# BEE_BOARD_DECAWAVE.net
KiCad netlist of a schematic drawn in Altium Designer
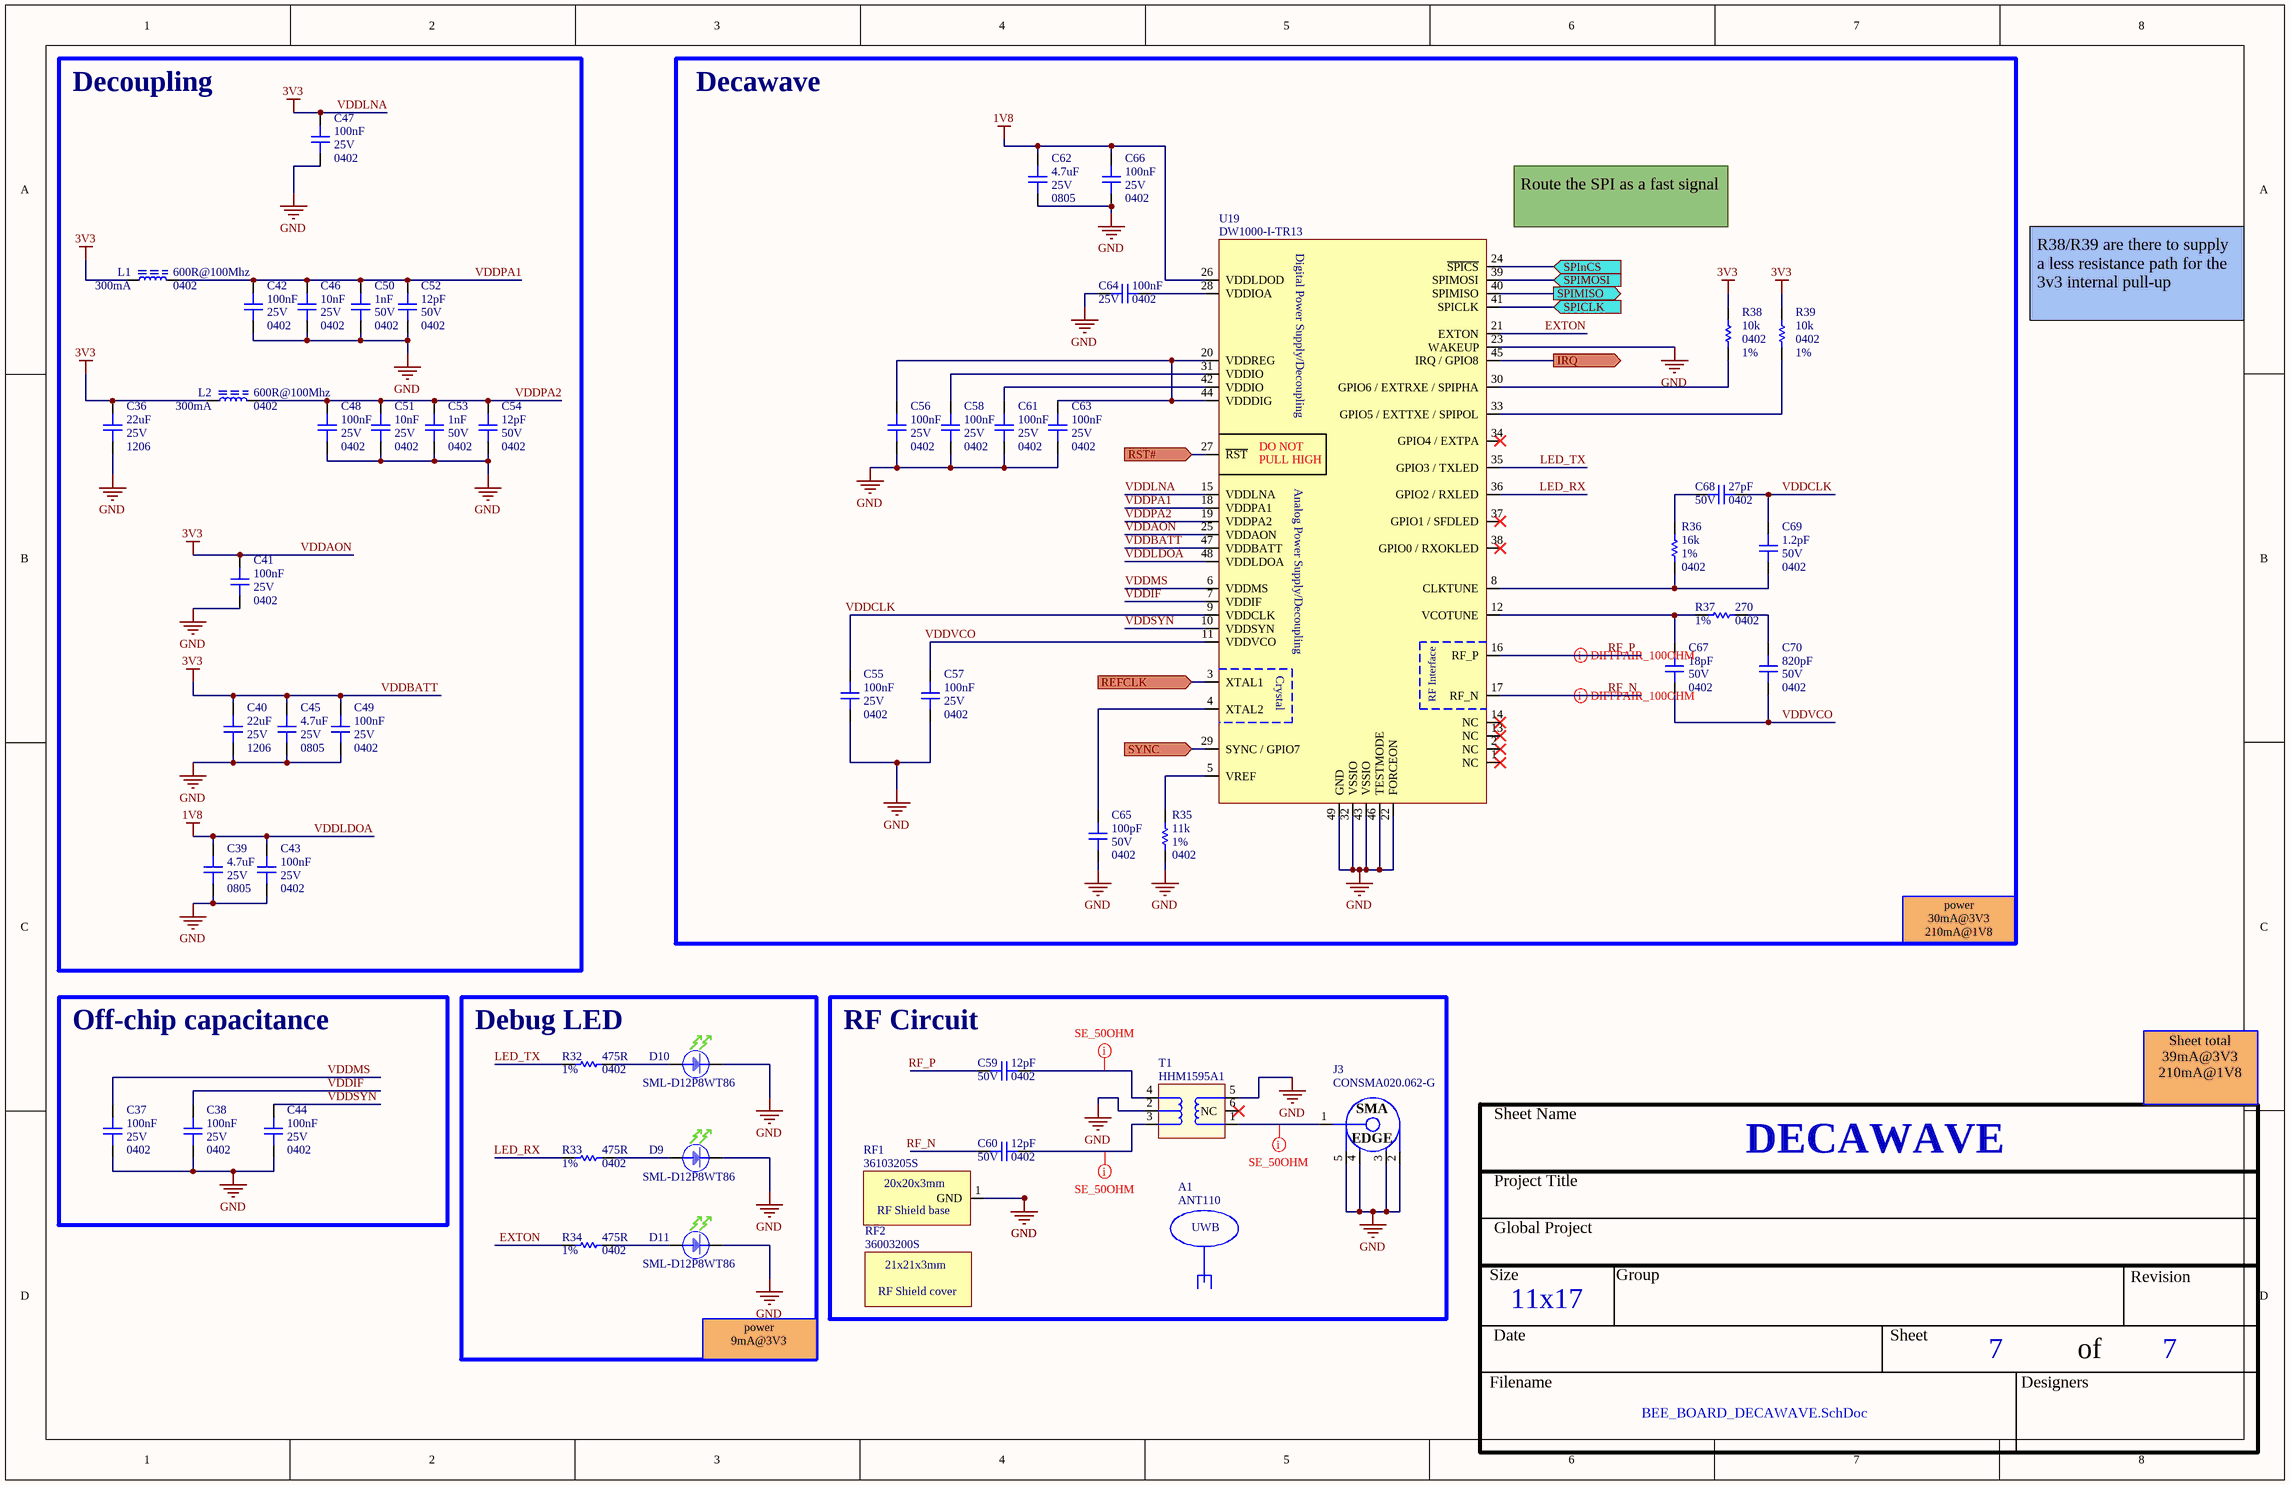
[diagram p0: BEE_BOARD_DECAWAVE.SchDoc]

(export (version "E")
  (design (tool "Eeschema 10.0.6"))
  (components
    (comp (ref "A1")
      (value "ANT110")
      (description "ANT - UWB antenna 3.2 to 7GHz")
      (fields
        (field (name "CREATEDBY/DATE") "Philippe Arsenault/2021-04-11")
        (field (name "VERIFIEDBY") "Louis-Daniel Gaulin / 14-04-2021")
      )
      (libsource (lib "SWARMUS_LIB") (part "ANT_ANT110"))
    )
    (comp (ref "C36")
      (value "22uF")
      (footprint "grams_master_lib_pcb:CAP_CER_1206")
      (description "CAP - CER 22uF 10% 25V X5R - 1206")
      (fields
        (field (name "TOLERANCE") "10%")
        (field (name "PACKAGE") "1206")
        (field (name "VOLTAGE RATING") "25V")
        (field (name "Comment") "CL31A226KAHNNNE")
        (field (name "CREATEDBY/DATE") "Philippe Arsenault/21 Janvier 2020")
        (field (name "VERIFIEDBY") "C.Paulin - 28/01/2020")
      )
      (libsource (lib "GRAMS_MASTER_LIB_SCH") (part "CAP_CER_CL31A226KAHNNNE"))
    )
    (comp (ref "C37")
      (value "100nF")
      (footprint "GRAMS_MASTER_LIB_PCB:CAP_CER_0402")
      (description "CAP - CER 0.1µF 10% 25V X7R - 0402")
      (fields
        (field (name "TOLERANCE") "10%")
        (field (name "PACKAGE") "0402")
        (field (name "VOLTAGE RATING") "25V")
        (field (name "Comment") "CGA2B3X7R1E104K050BB")
        (field (name "CREATEDBY/DATE") "Nicolas Roy 2018-11-07")
        (field (name "VERIFIEDBY") "Nicolas V. (2019-01-22)")
      )
      (libsource (lib "GRAMS_MASTER_LIB_SCH") (part "CAP_CER_CGA2B3X7R1E104K050BB"))
    )
    (comp (ref "C38")
      (value "100nF")
      (footprint "GRAMS_MASTER_LIB_PCB:CAP_CER_0402")
      (description "CAP - CER 0.1µF 10% 25V X7R - 0402")
      (fields
        (field (name "TOLERANCE") "10%")
        (field (name "PACKAGE") "0402")
        (field (name "VOLTAGE RATING") "25V")
        (field (name "Comment") "CGA2B3X7R1E104K050BB")
        (field (name "CREATEDBY/DATE") "Nicolas Roy 2018-11-07")
        (field (name "VERIFIEDBY") "Nicolas V. (2019-01-22)")
      )
      (libsource (lib "GRAMS_MASTER_LIB_SCH") (part "CAP_CER_CGA2B3X7R1E104K050BB"))
    )
    (comp (ref "C39")
      (value "4.7uF")
      (footprint "GRAMS_MASTER_LIB_PCB:CAP_CER_0805")
      (description "CAP - CER 4.7UF 10% 25V X7R - 0805")
      (fields
        (field (name "TOLERANCE") "10%")
        (field (name "PACKAGE") "0805")
        (field (name "VOLTAGE RATING") "25V")
        (field (name "Comment") "C2012X7R1E475K125AE")
        (field (name "CREATEDBY/DATE") "Keven Deslandes - 2018/11/09")
        (field (name "VERIFIEDBY") "Nicolas Roy - 2018/12/11")
      )
      (libsource (lib "GRAMS_MASTER_LIB_SCH") (part "CAP_CER_C2012X7R1E475K125AE"))
    )
    (comp (ref "C40")
      (value "22uF")
      (footprint "grams_master_lib_pcb:CAP_CER_1206")
      (description "CAP - CER 22uF 10% 25V X5R - 1206")
      (fields
        (field (name "TOLERANCE") "10%")
        (field (name "PACKAGE") "1206")
        (field (name "VOLTAGE RATING") "25V")
        (field (name "Comment") "CL31A226KAHNNNE")
        (field (name "CREATEDBY/DATE") "Philippe Arsenault/21 Janvier 2020")
        (field (name "VERIFIEDBY") "C.Paulin - 28/01/2020")
      )
      (libsource (lib "GRAMS_MASTER_LIB_SCH") (part "CAP_CER_CL31A226KAHNNNE"))
    )
    (comp (ref "C41")
      (value "100nF")
      (footprint "GRAMS_MASTER_LIB_PCB:CAP_CER_0402")
      (description "CAP - CER 0.1µF 10% 25V X7R - 0402")
      (fields
        (field (name "TOLERANCE") "10%")
        (field (name "PACKAGE") "0402")
        (field (name "VOLTAGE RATING") "25V")
        (field (name "Comment") "CGA2B3X7R1E104K050BB")
        (field (name "CREATEDBY/DATE") "Nicolas Roy 2018-11-07")
        (field (name "VERIFIEDBY") "Nicolas V. (2019-01-22)")
      )
      (libsource (lib "GRAMS_MASTER_LIB_SCH") (part "CAP_CER_CGA2B3X7R1E104K050BB"))
    )
    (comp (ref "C42")
      (value "100nF")
      (footprint "GRAMS_MASTER_LIB_PCB:CAP_CER_0402")
      (description "CAP - CER 0.1µF 10% 25V X7R - 0402")
      (fields
        (field (name "TOLERANCE") "10%")
        (field (name "PACKAGE") "0402")
        (field (name "VOLTAGE RATING") "25V")
        (field (name "Comment") "CGA2B3X7R1E104K050BB")
        (field (name "CREATEDBY/DATE") "Nicolas Roy 2018-11-07")
        (field (name "VERIFIEDBY") "Nicolas V. (2019-01-22)")
      )
      (libsource (lib "GRAMS_MASTER_LIB_SCH") (part "CAP_CER_CGA2B3X7R1E104K050BB"))
    )
    (comp (ref "C43")
      (value "100nF")
      (footprint "GRAMS_MASTER_LIB_PCB:CAP_CER_0402")
      (description "CAP - CER 0.1µF 10% 25V X7R - 0402")
      (fields
        (field (name "TOLERANCE") "10%")
        (field (name "PACKAGE") "0402")
        (field (name "VOLTAGE RATING") "25V")
        (field (name "Comment") "CGA2B3X7R1E104K050BB")
        (field (name "CREATEDBY/DATE") "Nicolas Roy 2018-11-07")
        (field (name "VERIFIEDBY") "Nicolas V. (2019-01-22)")
      )
      (libsource (lib "GRAMS_MASTER_LIB_SCH") (part "CAP_CER_CGA2B3X7R1E104K050BB"))
    )
    (comp (ref "C44")
      (value "100nF")
      (footprint "GRAMS_MASTER_LIB_PCB:CAP_CER_0402")
      (description "CAP - CER 0.1µF 10% 25V X7R - 0402")
      (fields
        (field (name "TOLERANCE") "10%")
        (field (name "PACKAGE") "0402")
        (field (name "VOLTAGE RATING") "25V")
        (field (name "Comment") "CGA2B3X7R1E104K050BB")
        (field (name "CREATEDBY/DATE") "Nicolas Roy 2018-11-07")
        (field (name "VERIFIEDBY") "Nicolas V. (2019-01-22)")
      )
      (libsource (lib "GRAMS_MASTER_LIB_SCH") (part "CAP_CER_CGA2B3X7R1E104K050BB"))
    )
    (comp (ref "C45")
      (value "4.7uF")
      (footprint "GRAMS_MASTER_LIB_PCB:CAP_CER_0805")
      (description "CAP - CER 4.7UF 10% 25V X7R - 0805")
      (fields
        (field (name "TOLERANCE") "10%")
        (field (name "PACKAGE") "0805")
        (field (name "VOLTAGE RATING") "25V")
        (field (name "Comment") "C2012X7R1E475K125AE")
        (field (name "CREATEDBY/DATE") "Keven Deslandes - 2018/11/09")
        (field (name "VERIFIEDBY") "Nicolas Roy - 2018/12/11")
      )
      (libsource (lib "GRAMS_MASTER_LIB_SCH") (part "CAP_CER_C2012X7R1E475K125AE"))
    )
    (comp (ref "C46")
      (value "10nF")
      (footprint "GRAMS_MASTER_LIB_PCB:CAP_CER_0402")
      (description "CAP - CER 10nF 10% 25V X7R - 0402")
      (fields
        (field (name "TOLERANCE") "10%")
        (field (name "PACKAGE") "0402")
        (field (name "VOLTAGE RATING") "25V")
        (field (name "Comment") "CL05B103KA5NNNC")
        (field (name "CREATEDBY/DATE") "Romain Espagnet 2018-07-16")
        (field (name "VERIFIEDBY") "Jonathan Bouchard 2018-07-30")
      )
      (libsource (lib "GRAMS_MASTER_LIB_SCH") (part "CAP_CER_CL05B103KA5NNNC"))
    )
    (comp (ref "C47")
      (value "100nF")
      (footprint "GRAMS_MASTER_LIB_PCB:CAP_CER_0402")
      (description "CAP - CER 0.1µF 10% 25V X7R - 0402")
      (fields
        (field (name "TOLERANCE") "10%")
        (field (name "PACKAGE") "0402")
        (field (name "VOLTAGE RATING") "25V")
        (field (name "Comment") "CGA2B3X7R1E104K050BB")
        (field (name "CREATEDBY/DATE") "Nicolas Roy 2018-11-07")
        (field (name "VERIFIEDBY") "Nicolas V. (2019-01-22)")
      )
      (libsource (lib "GRAMS_MASTER_LIB_SCH") (part "CAP_CER_CGA2B3X7R1E104K050BB"))
    )
    (comp (ref "C48")
      (value "100nF")
      (footprint "GRAMS_MASTER_LIB_PCB:CAP_CER_0402")
      (description "CAP - CER 0.1µF 10% 25V X7R - 0402")
      (fields
        (field (name "TOLERANCE") "10%")
        (field (name "PACKAGE") "0402")
        (field (name "VOLTAGE RATING") "25V")
        (field (name "Comment") "CGA2B3X7R1E104K050BB")
        (field (name "CREATEDBY/DATE") "Nicolas Roy 2018-11-07")
        (field (name "VERIFIEDBY") "Nicolas V. (2019-01-22)")
      )
      (libsource (lib "GRAMS_MASTER_LIB_SCH") (part "CAP_CER_CGA2B3X7R1E104K050BB"))
    )
    (comp (ref "C49")
      (value "100nF")
      (footprint "GRAMS_MASTER_LIB_PCB:CAP_CER_0402")
      (description "CAP - CER 0.1µF 10% 25V X7R - 0402")
      (fields
        (field (name "TOLERANCE") "10%")
        (field (name "PACKAGE") "0402")
        (field (name "VOLTAGE RATING") "25V")
        (field (name "Comment") "CGA2B3X7R1E104K050BB")
        (field (name "CREATEDBY/DATE") "Nicolas Roy 2018-11-07")
        (field (name "VERIFIEDBY") "Nicolas V. (2019-01-22)")
      )
      (libsource (lib "GRAMS_MASTER_LIB_SCH") (part "CAP_CER_CGA2B3X7R1E104K050BB"))
    )
    (comp (ref "C50")
      (value "1nF")
      (footprint "CAP_CER_0402")
      (description "CAP - CER 1nF 10% 50V X7R - 0402")
      (fields
        (field (name "TOLERANCE") "10%")
        (field (name "PACKAGE") "0402")
        (field (name "VOLTAGE RATING") "50V")
        (field (name "Comment") "CC0402KRX7R9BB102")
        (field (name "CREATEDBY/DATE") "Jonathan Bouchard 2019-04-06")
        (field (name "VERIFIEDBY") "Nicolas V. (2019-04-30)")
      )
      (libsource (lib "GRAMS_MASTER_LIB_SCH") (part "CAP_CER_CC0402KRX7R9BB102"))
    )
    (comp (ref "C51")
      (value "10nF")
      (footprint "GRAMS_MASTER_LIB_PCB:CAP_CER_0402")
      (description "CAP - CER 10nF 10% 25V X7R - 0402")
      (fields
        (field (name "TOLERANCE") "10%")
        (field (name "PACKAGE") "0402")
        (field (name "VOLTAGE RATING") "25V")
        (field (name "Comment") "CL05B103KA5NNNC")
        (field (name "CREATEDBY/DATE") "Romain Espagnet 2018-07-16")
        (field (name "VERIFIEDBY") "Jonathan Bouchard 2018-07-30")
      )
      (libsource (lib "GRAMS_MASTER_LIB_SCH") (part "CAP_CER_CL05B103KA5NNNC"))
    )
    (comp (ref "C52")
      (value "12pF")
      (footprint "SWARMUS_LIB:CAP_CER_0402")
      (description "CAP - CER 12pF 50V ±5% C0G, NP0 - 0402")
      (fields
        (field (name "TOLERANCE") "±5%")
        (field (name "PACKAGE") "0402")
        (field (name "VOLTAGE RATING") "50V")
        (field (name "Comment") "CC0402JRNPO9BN120")
        (field (name "CREATEDBY/DATE") "Philippe Arsenault/ 2020-07-24")
        (field (name "VERIFIEDBY") "Louis-Daniel Gaulin / 2020-07-29")
      )
      (libsource (lib "SWARMUS_LIB") (part "CAP_CER_CC0402JRNPO9BN120"))
    )
    (comp (ref "C53")
      (value "1nF")
      (footprint "CAP_CER_0402")
      (description "CAP - CER 1nF 10% 50V X7R - 0402")
      (fields
        (field (name "TOLERANCE") "10%")
        (field (name "PACKAGE") "0402")
        (field (name "VOLTAGE RATING") "50V")
        (field (name "Comment") "CC0402KRX7R9BB102")
        (field (name "CREATEDBY/DATE") "Jonathan Bouchard 2019-04-06")
        (field (name "VERIFIEDBY") "Nicolas V. (2019-04-30)")
      )
      (libsource (lib "GRAMS_MASTER_LIB_SCH") (part "CAP_CER_CC0402KRX7R9BB102"))
    )
    (comp (ref "C54")
      (value "12pF")
      (footprint "SWARMUS_LIB:CAP_CER_0402")
      (description "CAP - CER 12pF 50V ±5% C0G, NP0 - 0402")
      (fields
        (field (name "TOLERANCE") "±5%")
        (field (name "PACKAGE") "0402")
        (field (name "VOLTAGE RATING") "50V")
        (field (name "Comment") "CC0402JRNPO9BN120")
        (field (name "CREATEDBY/DATE") "Philippe Arsenault/ 2020-07-24")
        (field (name "VERIFIEDBY") "Louis-Daniel Gaulin / 2020-07-29")
      )
      (libsource (lib "SWARMUS_LIB") (part "CAP_CER_CC0402JRNPO9BN120"))
    )
    (comp (ref "C55")
      (value "100nF")
      (footprint "GRAMS_MASTER_LIB_PCB:CAP_CER_0402")
      (description "CAP - CER 0.1µF 10% 25V X7R - 0402")
      (fields
        (field (name "TOLERANCE") "10%")
        (field (name "PACKAGE") "0402")
        (field (name "VOLTAGE RATING") "25V")
        (field (name "Comment") "CGA2B3X7R1E104K050BB")
        (field (name "CREATEDBY/DATE") "Nicolas Roy 2018-11-07")
        (field (name "VERIFIEDBY") "Nicolas V. (2019-01-22)")
      )
      (libsource (lib "GRAMS_MASTER_LIB_SCH") (part "CAP_CER_CGA2B3X7R1E104K050BB"))
    )
    (comp (ref "C56")
      (value "100nF")
      (footprint "GRAMS_MASTER_LIB_PCB:CAP_CER_0402")
      (description "CAP - CER 0.1µF 10% 25V X7R - 0402")
      (fields
        (field (name "TOLERANCE") "10%")
        (field (name "PACKAGE") "0402")
        (field (name "VOLTAGE RATING") "25V")
        (field (name "Comment") "CGA2B3X7R1E104K050BB")
        (field (name "CREATEDBY/DATE") "Nicolas Roy 2018-11-07")
        (field (name "VERIFIEDBY") "Nicolas V. (2019-01-22)")
      )
      (libsource (lib "GRAMS_MASTER_LIB_SCH") (part "CAP_CER_CGA2B3X7R1E104K050BB"))
    )
    (comp (ref "C57")
      (value "100nF")
      (footprint "GRAMS_MASTER_LIB_PCB:CAP_CER_0402")
      (description "CAP - CER 0.1µF 10% 25V X7R - 0402")
      (fields
        (field (name "TOLERANCE") "10%")
        (field (name "PACKAGE") "0402")
        (field (name "VOLTAGE RATING") "25V")
        (field (name "Comment") "CGA2B3X7R1E104K050BB")
        (field (name "CREATEDBY/DATE") "Nicolas Roy 2018-11-07")
        (field (name "VERIFIEDBY") "Nicolas V. (2019-01-22)")
      )
      (libsource (lib "GRAMS_MASTER_LIB_SCH") (part "CAP_CER_CGA2B3X7R1E104K050BB"))
    )
    (comp (ref "C58")
      (value "100nF")
      (footprint "GRAMS_MASTER_LIB_PCB:CAP_CER_0402")
      (description "CAP - CER 0.1µF 10% 25V X7R - 0402")
      (fields
        (field (name "TOLERANCE") "10%")
        (field (name "PACKAGE") "0402")
        (field (name "VOLTAGE RATING") "25V")
        (field (name "Comment") "CGA2B3X7R1E104K050BB")
        (field (name "CREATEDBY/DATE") "Nicolas Roy 2018-11-07")
        (field (name "VERIFIEDBY") "Nicolas V. (2019-01-22)")
      )
      (libsource (lib "GRAMS_MASTER_LIB_SCH") (part "CAP_CER_CGA2B3X7R1E104K050BB"))
    )
    (comp (ref "C59")
      (value "12pF")
      (footprint "SWARMUS_LIB:CAP_CER_0402")
      (description "CAP - CER 12pF 50V ±5% C0G, NP0 - 0402")
      (fields
        (field (name "TOLERANCE") "±5%")
        (field (name "PACKAGE") "0402")
        (field (name "VOLTAGE RATING") "50V")
        (field (name "Comment") "CC0402JRNPO9BN120")
        (field (name "CREATEDBY/DATE") "Philippe Arsenault/ 2020-07-24")
        (field (name "VERIFIEDBY") "Louis-Daniel Gaulin / 2020-07-29")
      )
      (libsource (lib "SWARMUS_LIB") (part "CAP_CER_CC0402JRNPO9BN120"))
    )
    (comp (ref "C60")
      (value "12pF")
      (footprint "SWARMUS_LIB:CAP_CER_0402")
      (description "CAP - CER 12pF 50V ±5% C0G, NP0 - 0402")
      (fields
        (field (name "TOLERANCE") "±5%")
        (field (name "PACKAGE") "0402")
        (field (name "VOLTAGE RATING") "50V")
        (field (name "Comment") "CC0402JRNPO9BN120")
        (field (name "CREATEDBY/DATE") "Philippe Arsenault/ 2020-07-24")
        (field (name "VERIFIEDBY") "Louis-Daniel Gaulin / 2020-07-29")
      )
      (libsource (lib "SWARMUS_LIB") (part "CAP_CER_CC0402JRNPO9BN120"))
    )
    (comp (ref "C61")
      (value "100nF")
      (footprint "GRAMS_MASTER_LIB_PCB:CAP_CER_0402")
      (description "CAP - CER 0.1µF 10% 25V X7R - 0402")
      (fields
        (field (name "TOLERANCE") "10%")
        (field (name "PACKAGE") "0402")
        (field (name "VOLTAGE RATING") "25V")
        (field (name "Comment") "CGA2B3X7R1E104K050BB")
        (field (name "CREATEDBY/DATE") "Nicolas Roy 2018-11-07")
        (field (name "VERIFIEDBY") "Nicolas V. (2019-01-22)")
      )
      (libsource (lib "GRAMS_MASTER_LIB_SCH") (part "CAP_CER_CGA2B3X7R1E104K050BB"))
    )
    (comp (ref "C62")
      (value "4.7uF")
      (footprint "GRAMS_MASTER_LIB_PCB:CAP_CER_0805")
      (description "CAP - CER 4.7UF 10% 25V X7R - 0805")
      (fields
        (field (name "TOLERANCE") "10%")
        (field (name "PACKAGE") "0805")
        (field (name "VOLTAGE RATING") "25V")
        (field (name "Comment") "C2012X7R1E475K125AE")
        (field (name "CREATEDBY/DATE") "Keven Deslandes - 2018/11/09")
        (field (name "VERIFIEDBY") "Nicolas Roy - 2018/12/11")
      )
      (libsource (lib "GRAMS_MASTER_LIB_SCH") (part "CAP_CER_C2012X7R1E475K125AE"))
    )
    (comp (ref "C63")
      (value "100nF")
      (footprint "GRAMS_MASTER_LIB_PCB:CAP_CER_0402")
      (description "CAP - CER 0.1µF 10% 25V X7R - 0402")
      (fields
        (field (name "TOLERANCE") "10%")
        (field (name "PACKAGE") "0402")
        (field (name "VOLTAGE RATING") "25V")
        (field (name "Comment") "CGA2B3X7R1E104K050BB")
        (field (name "CREATEDBY/DATE") "Nicolas Roy 2018-11-07")
        (field (name "VERIFIEDBY") "Nicolas V. (2019-01-22)")
      )
      (libsource (lib "GRAMS_MASTER_LIB_SCH") (part "CAP_CER_CGA2B3X7R1E104K050BB"))
    )
    (comp (ref "C64")
      (value "100nF")
      (footprint "GRAMS_MASTER_LIB_PCB:CAP_CER_0402")
      (description "CAP - CER 0.1µF 10% 25V X7R - 0402")
      (fields
        (field (name "TOLERANCE") "10%")
        (field (name "PACKAGE") "0402")
        (field (name "VOLTAGE RATING") "25V")
        (field (name "Comment") "CGA2B3X7R1E104K050BB")
        (field (name "CREATEDBY/DATE") "Nicolas Roy 2018-11-07")
        (field (name "VERIFIEDBY") "Nicolas V. (2019-01-22)")
      )
      (libsource (lib "GRAMS_MASTER_LIB_SCH") (part "CAP_CER_CGA2B3X7R1E104K050BB"))
    )
    (comp (ref "C65")
      (value "100pF")
      (footprint "SWARMUS_LIB:CAP_CER_0402")
      (description "CAP - CER 100pF 50V ±5% C0G,CP0 - 0402")
      (fields
        (field (name "TOLERANCE") "±5%")
        (field (name "PACKAGE") "0402")
        (field (name "VOLTAGE RATING") "50V")
        (field (name "Comment") "CC0402JRNPO9BN101")
        (field (name "CREATEDBY/DATE") "Philippe Arsenault/ 2020-07-24")
        (field (name "VERIFIEDBY") "Louis-Daniel Gaulin / 2020-07-29")
      )
      (libsource (lib "SWARMUS_LIB") (part "CAP_CER_CC0402JRNPO9BN101"))
    )
    (comp (ref "C66")
      (value "100nF")
      (footprint "GRAMS_MASTER_LIB_PCB:CAP_CER_0402")
      (description "CAP - CER 0.1µF 10% 25V X7R - 0402")
      (fields
        (field (name "TOLERANCE") "10%")
        (field (name "PACKAGE") "0402")
        (field (name "VOLTAGE RATING") "25V")
        (field (name "Comment") "CGA2B3X7R1E104K050BB")
        (field (name "CREATEDBY/DATE") "Nicolas Roy 2018-11-07")
        (field (name "VERIFIEDBY") "Nicolas V. (2019-01-22)")
      )
      (libsource (lib "GRAMS_MASTER_LIB_SCH") (part "CAP_CER_CGA2B3X7R1E104K050BB"))
    )
    (comp (ref "C67")
      (value "18pF")
      (footprint "CAP_CER_0402")
      (description "CAP - CER 18pF 50V C0G, NPO - 0402")
      (fields
        (field (name "TOLERANCE") "2%")
        (field (name "PACKAGE") "0402")
        (field (name "VOLTAGE RATING") "50V")
        (field (name "Comment") "GRM1555C1H180GA01D")
        (field (name "CREATEDBY/DATE") "Tommy Rossignol / 2018-11-20")
        (field (name "VERIFIEDBY") "Caroline Paulin - 13 fév 2019")
      )
      (libsource (lib "GRAMS_MASTER_LIB_SCH") (part "CAP_CER_GRM1555C1H180GA01D"))
    )
    (comp (ref "C68")
      (value "27pF")
      (footprint "SWARMUS_LIB:CAP_CER_0402")
      (description "CAP - CER 27pF 50V ±5% C0G, NP0 - 0402")
      (fields
        (field (name "TOLERANCE") "±5%")
        (field (name "PACKAGE") "0402")
        (field (name "VOLTAGE RATING") "50V")
        (field (name "Comment") "CC0402JRNPO9BN270")
        (field (name "CREATEDBY/DATE") "Philippe Arsenault/ 2020-07-24")
        (field (name "VERIFIEDBY") "Louis-Daniel Gaulin / 2020-07-29")
      )
      (libsource (lib "SWARMUS_LIB") (part "CAP_CER_CC0402JRNPO9BN270"))
    )
    (comp (ref "C69")
      (value "1.2pF")
      (footprint "SWARMUS_LIB:CAP_CER_0402")
      (description "CAP - CER 1.2pF 50V ±0.25pF C0G, NP0 - 0402")
      (fields
        (field (name "TOLERANCE") "±0.25pF")
        (field (name "PACKAGE") "0402")
        (field (name "VOLTAGE RATING") "50V")
        (field (name "Comment") "C0402C129C5GACTU")
        (field (name "CREATEDBY/DATE") "Philippe Arsenault/ 2020-07-24")
        (field (name "VERIFIEDBY") "Louis-Daniel Gaulin / 2020-07-29")
      )
      (libsource (lib "SWARMUS_LIB") (part "CAP_CER_C0402C129C5GACTU"))
    )
    (comp (ref "C70")
      (value "820pF")
      (footprint "SWARMUS_LIB:CAP_CER_0402")
      (description "CAP - CER 820pF 50V ±10% X7R - 0402")
      (fields
        (field (name "TOLERANCE") "±10%")
        (field (name "PACKAGE") "0402")
        (field (name "VOLTAGE RATING") "50V")
        (field (name "Comment") "CC0402KRX7R9BB821")
        (field (name "CREATEDBY/DATE") "Philippe Arsenault/ 2020-07-24")
        (field (name "VERIFIEDBY") "Louis-Daniel Gaulin / 2020-07-29")
      )
      (libsource (lib "SWARMUS_LIB") (part "CAP_CER_CC0402KRX7R9BB821"))
    )
    (comp (ref "D9")
      (value "SML-D12P8WT86")
      (footprint "GRAMS_MASTER_LIB_PCB:LED_SML-D12P8WT86")
      (description "LED - GREEN DIFFUSED 0603 SMD - 0603")
      (fields
        (field (name "CREATEDBY/DATE") "Keven Deslandes - 2018/11/21")
        (field (name "VERIFIEDBY") "Caroline Paulin - 13 février 2019")
      )
      (libsource (lib "GRAMS_MASTER_LIB_SCH") (part "LED_SML-D12P8WT86"))
    )
    (comp (ref "D10")
      (value "SML-D12P8WT86")
      (footprint "GRAMS_MASTER_LIB_PCB:LED_SML-D12P8WT86")
      (description "LED - GREEN DIFFUSED 0603 SMD - 0603")
      (fields
        (field (name "CREATEDBY/DATE") "Keven Deslandes - 2018/11/21")
        (field (name "VERIFIEDBY") "Caroline Paulin - 13 février 2019")
      )
      (libsource (lib "GRAMS_MASTER_LIB_SCH") (part "LED_SML-D12P8WT86"))
    )
    (comp (ref "D11")
      (value "SML-D12P8WT86")
      (footprint "GRAMS_MASTER_LIB_PCB:LED_SML-D12P8WT86")
      (description "LED - GREEN DIFFUSED 0603 SMD - 0603")
      (fields
        (field (name "CREATEDBY/DATE") "Keven Deslandes - 2018/11/21")
        (field (name "VERIFIEDBY") "Caroline Paulin - 13 février 2019")
      )
      (libsource (lib "GRAMS_MASTER_LIB_SCH") (part "LED_SML-D12P8WT86"))
    )
    (comp (ref "J3")
      (value "CONSMA020.062-G")
      (footprint "CON_SMA_CONSMA020.062-G")
      (description "CON_SMA FML EDGE MNT 0.062\" PCB - 5-SMD")
      (fields (field (name "CREATEDBY/DATE") "Philippe Arsenault/2021-03-26"))
      (libsource (lib "SWARMUS_LIB") (part "CON_SMA_CONSMA020.062-G"))
    )
    (comp (ref "L1")
      (value "600R@100Mhz")
      (footprint "FER_0402")
      (description "FER - FERRITE BEAD 600 OHM@100MHz - 0402")
      (fields
        (field (name "CURRENT RATING") "300mA")
        (field (name "PACKAGE") "0402")
        (field (name "Comment") "BLM15AG601SN1D")
        (field (name "CREATEDBY/DATE") "Philippe Arsenault/2020-07-24")
      )
      (libsource (lib "a_Valider_PA") (part "FER_BLM15AG601SN1D"))
    )
    (comp (ref "L2")
      (value "600R@100Mhz")
      (footprint "FER_0402")
      (description "FER - FERRITE BEAD 600 OHM@100MHz - 0402")
      (fields
        (field (name "CURRENT RATING") "300mA")
        (field (name "PACKAGE") "0402")
        (field (name "Comment") "BLM15AG601SN1D")
        (field (name "CREATEDBY/DATE") "Philippe Arsenault/2020-07-24")
      )
      (libsource (lib "a_Valider_PA") (part "FER_BLM15AG601SN1D"))
    )
    (comp (ref "R32")
      (value "475R")
      (footprint "GRAMS_MASTER_LIB_PCB:RES_0402")
      (description "RES - 475R 1% 1/10W- 0402")
      (fields
        (field (name "TOLERANCE") "1%")
        (field (name "PACKAGE") "0402")
        (field (name "Comment") "ERJ-2RKF4750X")
        (field (name "CREATEDBY/DATE") "Keven Deslandes 2018-10-17")
        (field (name "VERIFIEDBY") "Carolilne Paulin - 18/12/2018")
      )
      (libsource (lib "GRAMS_MASTER_LIB_SCH") (part "RES_ERJ-2RKF4750X"))
    )
    (comp (ref "R33")
      (value "475R")
      (footprint "GRAMS_MASTER_LIB_PCB:RES_0402")
      (description "RES - 475R 1% 1/10W- 0402")
      (fields
        (field (name "TOLERANCE") "1%")
        (field (name "PACKAGE") "0402")
        (field (name "Comment") "ERJ-2RKF4750X")
        (field (name "CREATEDBY/DATE") "Keven Deslandes 2018-10-17")
        (field (name "VERIFIEDBY") "Carolilne Paulin - 18/12/2018")
      )
      (libsource (lib "GRAMS_MASTER_LIB_SCH") (part "RES_ERJ-2RKF4750X"))
    )
    (comp (ref "R34")
      (value "475R")
      (footprint "GRAMS_MASTER_LIB_PCB:RES_0402")
      (description "RES - 475R 1% 1/10W- 0402")
      (fields
        (field (name "TOLERANCE") "1%")
        (field (name "PACKAGE") "0402")
        (field (name "Comment") "ERJ-2RKF4750X")
        (field (name "CREATEDBY/DATE") "Keven Deslandes 2018-10-17")
        (field (name "VERIFIEDBY") "Carolilne Paulin - 18/12/2018")
      )
      (libsource (lib "GRAMS_MASTER_LIB_SCH") (part "RES_ERJ-2RKF4750X"))
    )
    (comp (ref "R35")
      (value "11k")
      (footprint "GRAMS_MASTER_LIB_PCB:RES_0402")
      (description "RES - 11K 1% 1/16W - 0402")
      (fields
        (field (name "TOLERANCE") "1%")
        (field (name "PACKAGE") "0402")
        (field (name "Comment") "RC0402FR-0711KL")
        (field (name "CREATEDBY/DATE") "Keven Deslandes 2018-10-15")
        (field (name "VERIFIEDBY") "Carolilne Paulin - 18/12/2018")
      )
      (libsource (lib "GRAMS_MASTER_LIB_SCH") (part "RES_RC0402FR-0711KL"))
    )
    (comp (ref "R36")
      (value "16k")
      (footprint "GRAMS_MASTER_LIB_PCB:RES_0402")
      (description "RES - 16k OHM 1% 1/16W - 0402")
      (fields
        (field (name "TOLERANCE") "1%")
        (field (name "PACKAGE") "0402")
        (field (name "Comment") "RC0402FR-0716KL")
        (field (name "CREATEDBY/DATE") "Nicolas Roy/18 oct. 2018")
        (field (name "VERIFIEDBY") "Caroline Paulin - 18/12/2018")
      )
      (libsource (lib "GRAMS_MASTER_LIB_SCH") (part "RES_RC0402FR-0716KL"))
    )
    (comp (ref "R37")
      (value "270")
      (footprint "FER_0402")
      (description "RES - 270R 1% 1/16W - 0402")
      (fields
        (field (name "TOLERANCE") "1%")
        (field (name "PACKAGE") "0402")
        (field (name "Comment") "RC0402FR-07270RL")
        (field (name "CREATEDBY/DATE") "Philippe Arsenault 2020-07-24")
        (field (name "VERIFIEDBY") "Louis-Daniel Gaulin / 03-10-2020")
      )
      (libsource (lib "SWARMUS_LIB") (part "RES_RC0402FR-07270RL"))
    )
    (comp (ref "R38")
      (value "10k")
      (footprint "GRAMS_MASTER_LIB_PCB:RES_0402")
      (description "RES - 10K OHMS 1% 1/16W - 0402")
      (fields
        (field (name "TOLERANCE") "1%")
        (field (name "PACKAGE") "0402")
        (field (name "Comment") "RC0402FR-0710KL")
        (field (name "CREATEDBY/DATE") "Nicolas V. (2018-11-20)")
        (field (name "VERIFIEDBY") "Nicolas V. (2018-11-20)")
      )
      (libsource (lib "GRAMS_MASTER_LIB_SCH") (part "RES_RC0402FR-0710KL"))
    )
    (comp (ref "R39")
      (value "10k")
      (footprint "GRAMS_MASTER_LIB_PCB:RES_0402")
      (description "RES - 10K OHMS 1% 1/16W - 0402")
      (fields
        (field (name "TOLERANCE") "1%")
        (field (name "PACKAGE") "0402")
        (field (name "Comment") "RC0402FR-0710KL")
        (field (name "CREATEDBY/DATE") "Nicolas V. (2018-11-20)")
        (field (name "VERIFIEDBY") "Nicolas V. (2018-11-20)")
      )
      (libsource (lib "GRAMS_MASTER_LIB_SCH") (part "RES_RC0402FR-0710KL"))
    )
    (comp (ref "RF1")
      (value "36103205S")
      (footprint "RF_SH_BASE_36103205S")
      (description "RF_SH -  BASE RF SHIELD 0.787\" X 0.787\" SMD")
      (fields
        (field (name "CREATEDBY/DATE") "Philippe Arsenault/2021-04-17")
        (field (name "VERIFIEDBY") "Louis-Daniel Gaulin / 29-04-2021")
      )
      (libsource (lib "SWARMUS_LIB") (part "RF_SH_BASE_36103205S"))
    )
    (comp (ref "RF2")
      (value "36003200S")
      (footprint "RF_SH_COVER_36003200S")
      (description "RF_SH -  RF COVER 0.823\" X 0.823\" SMD")
      (fields
        (field (name "CREATEDBY/DATE") "Philippe Arsenault/2021-04-17")
        (field (name "VERIFIEDBY") "Louis-Daniel Gaulin / 29-04-2021")
      )
      (libsource (lib "SWARMUS_LIB") (part "RF_SH_COVER_36003200S"))
    )
    (comp (ref "T1")
      (value "HHM1595A1")
      (footprint "XFR_HHM1595A1")
      (description "XFR - Imp Unbalaced/Balanced 50/100 3-8GHz  -SMD")
      (fields
        (field (name "CREATEDBY/DATE") "Philippe Arsenault/2020-21-07")
        (field (name "VERIFIEDBY") "Louis-Daniel Gaulin / 03-10-2020")
      )
      (libsource (lib "SWARMUS_LIB") (part "XFR_HHM1595A1"))
    )
    (comp (ref "U19")
      (value "DW1000-I-TR13")
      (footprint "SWARMUS_LIB:COM_XCV_DW1000-I-TR13")
      (description "COM - IC RF TxRx 802.15.4 IR-UWB DECAWAVE - 48-VFQFN EP")
      (fields (field (name "CREATEDBY/DATE") "Philippe Arsenault/13-07-2020"))
      (libsource (lib "SWARMUS_LIB") (part "COM_XCV_DW1000-I-TR13"))
    )
  )
  (nets
    (net (code "1") (name "/EXTON") (class "Default")
      (node (ref "R34") (pin "2") (pinfunction "2_2") (pintype "passive"))
      (node (ref "U19") (pin "21") (pinfunction "EXTON_21") (pintype "passive"))
    )
    (net (code "2") (name "/IRQ") (class "Default")
      (node (ref "U19") (pin "45") (pinfunction "IRQ_/_GPIO8_45") (pintype "passive"))
    )
    (net (code "3") (name "/LED_RX") (class "Default")
      (node (ref "R33") (pin "2") (pinfunction "2_2") (pintype "passive"))
      (node (ref "U19") (pin "36") (pinfunction "GPIO2_/_RXLED_36") (pintype "passive"))
    )
    (net (code "4") (name "/LED_TX") (class "Default")
      (node (ref "R32") (pin "2") (pinfunction "2_2") (pintype "passive"))
      (node (ref "U19") (pin "35") (pinfunction "GPIO3_/_TXLED_35") (pintype "passive"))
    )
    (net (code "5") (name "/REFCLK") (class "Default")
      (node (ref "U19") (pin "3") (pinfunction "XTAL1_3") (pintype "passive"))
    )
    (net (code "6") (name "/RF_N") (class "Default")
      (node (ref "C60") (pin "2") (pinfunction "2_2") (pintype "passive"))
      (node (ref "U19") (pin "17") (pinfunction "RF_N_17") (pintype "passive"))
    )
    (net (code "7") (name "/RF_P") (class "Default")
      (node (ref "C59") (pin "2") (pinfunction "2_2") (pintype "passive"))
      (node (ref "U19") (pin "16") (pinfunction "RF_P_16") (pintype "passive"))
    )
    (net (code "8") (name "/RST#") (class "Default")
      (node (ref "U19") (pin "27") (pinfunction "RST_27") (pintype "passive"))
    )
    (net (code "9") (name "/SPICLK") (class "Default")
      (node (ref "U19") (pin "41") (pinfunction "SPICLK_41") (pintype "passive"))
    )
    (net (code "10") (name "/SPIMISO") (class "Default")
      (node (ref "U19") (pin "40") (pinfunction "SPIMISO_40") (pintype "passive"))
    )
    (net (code "11") (name "/SPIMOSI") (class "Default")
      (node (ref "U19") (pin "39") (pinfunction "SPIMOSI_39") (pintype "passive"))
    )
    (net (code "12") (name "/SPInCS") (class "Default")
      (node (ref "U19") (pin "24") (pinfunction "SPICS_24") (pintype "passive"))
    )
    (net (code "13") (name "/SYNC") (class "Default")
      (node (ref "U19") (pin "29") (pinfunction "SYNC_/_GPIO7_29") (pintype "passive"))
    )
    (net (code "14") (name "/VDDCLK") (class "Default")
      (node (ref "C55") (pin "2") (pinfunction "2_2") (pintype "passive"))
      (node (ref "C68") (pin "1") (pinfunction "1_1") (pintype "passive"))
      (node (ref "C69") (pin "2") (pinfunction "2_2") (pintype "passive"))
      (node (ref "U19") (pin "9") (pinfunction "VDDCLK_9") (pintype "passive"))
    )
    (net (code "15") (name "/VDDIF") (class "Default")
      (node (ref "C38") (pin "2") (pinfunction "2_2") (pintype "passive"))
      (node (ref "U19") (pin "7") (pinfunction "VDDIF_7") (pintype "passive"))
    )
    (net (code "16") (name "/VDDMS") (class "Default")
      (node (ref "C37") (pin "2") (pinfunction "2_2") (pintype "passive"))
      (node (ref "U19") (pin "6") (pinfunction "VDDMS_6") (pintype "passive"))
    )
    (net (code "17") (name "/VDDPA1") (class "Default")
      (node (ref "C42") (pin "2") (pinfunction "2_2") (pintype "passive"))
      (node (ref "C46") (pin "2") (pinfunction "2_2") (pintype "passive"))
      (node (ref "C50") (pin "2") (pinfunction "2_2") (pintype "passive"))
      (node (ref "C52") (pin "2") (pinfunction "2_2") (pintype "passive"))
      (node (ref "L1") (pin "2") (pinfunction "2_2") (pintype "passive"))
      (node (ref "U19") (pin "18") (pinfunction "VDDPA1_18") (pintype "passive"))
    )
    (net (code "18") (name "/VDDPA2") (class "Default")
      (node (ref "C48") (pin "2") (pinfunction "2_2") (pintype "passive"))
      (node (ref "C51") (pin "2") (pinfunction "2_2") (pintype "passive"))
      (node (ref "C53") (pin "2") (pinfunction "2_2") (pintype "passive"))
      (node (ref "C54") (pin "2") (pinfunction "2_2") (pintype "passive"))
      (node (ref "L2") (pin "2") (pinfunction "2_2") (pintype "passive"))
      (node (ref "U19") (pin "19") (pinfunction "VDDPA2_19") (pintype "passive"))
    )
    (net (code "19") (name "/VDDSYN") (class "Default")
      (node (ref "C44") (pin "2") (pinfunction "2_2") (pintype "passive"))
      (node (ref "U19") (pin "10") (pinfunction "VDDSYN_10") (pintype "passive"))
    )
    (net (code "20") (name "/VDDVCO") (class "Default")
      (node (ref "C57") (pin "2") (pinfunction "2_2") (pintype "passive"))
      (node (ref "C67") (pin "1") (pinfunction "1_1") (pintype "passive"))
      (node (ref "C70") (pin "1") (pinfunction "1_1") (pintype "passive"))
      (node (ref "U19") (pin "11") (pinfunction "VDDVCO_11") (pintype "passive"))
    )
    (net (code "21") (name "1V8") (class "Default")
      (node (ref "C39") (pin "2") (pinfunction "2_2") (pintype "passive"))
      (node (ref "C43") (pin "2") (pinfunction "2_2") (pintype "passive"))
      (node (ref "C62") (pin "2") (pinfunction "2_2") (pintype "passive"))
      (node (ref "C66") (pin "2") (pinfunction "2_2") (pintype "passive"))
      (node (ref "U19") (pin "26") (pinfunction "VDDLDOD_26") (pintype "passive"))
      (node (ref "U19") (pin "48") (pinfunction "VDDLDOA_48") (pintype "passive"))
    )
    (net (code "22") (name "3V3") (class "Default")
      (node (ref "C36") (pin "2") (pinfunction "2_2") (pintype "passive"))
      (node (ref "C40") (pin "2") (pinfunction "2_2") (pintype "passive"))
      (node (ref "C41") (pin "2") (pinfunction "2_2") (pintype "passive"))
      (node (ref "C45") (pin "2") (pinfunction "2_2") (pintype "passive"))
      (node (ref "C47") (pin "2") (pinfunction "2_2") (pintype "passive"))
      (node (ref "C49") (pin "2") (pinfunction "2_2") (pintype "passive"))
      (node (ref "L1") (pin "1") (pinfunction "1_1") (pintype "passive"))
      (node (ref "L2") (pin "1") (pinfunction "1_1") (pintype "passive"))
      (node (ref "R38") (pin "1") (pinfunction "1_1") (pintype "passive"))
      (node (ref "R39") (pin "1") (pinfunction "1_1") (pintype "passive"))
      (node (ref "U19") (pin "15") (pinfunction "VDDLNA_15") (pintype "passive"))
      (node (ref "U19") (pin "25") (pinfunction "VDDAON_25") (pintype "passive"))
      (node (ref "U19") (pin "47") (pinfunction "VDDBATT_47") (pintype "passive"))
    )
    (net (code "23") (name "GND") (class "Default")
      (node (ref "C36") (pin "1") (pinfunction "1_1") (pintype "passive"))
      (node (ref "C37") (pin "1") (pinfunction "1_1") (pintype "passive"))
      (node (ref "C38") (pin "1") (pinfunction "1_1") (pintype "passive"))
      (node (ref "C39") (pin "1") (pinfunction "1_1") (pintype "passive"))
      (node (ref "C40") (pin "1") (pinfunction "1_1") (pintype "passive"))
      (node (ref "C41") (pin "1") (pinfunction "1_1") (pintype "passive"))
      (node (ref "C42") (pin "1") (pinfunction "1_1") (pintype "passive"))
      (node (ref "C43") (pin "1") (pinfunction "1_1") (pintype "passive"))
      (node (ref "C44") (pin "1") (pinfunction "1_1") (pintype "passive"))
      (node (ref "C45") (pin "1") (pinfunction "1_1") (pintype "passive"))
      (node (ref "C46") (pin "1") (pinfunction "1_1") (pintype "passive"))
      (node (ref "C47") (pin "1") (pinfunction "1_1") (pintype "passive"))
      (node (ref "C48") (pin "1") (pinfunction "1_1") (pintype "passive"))
      (node (ref "C49") (pin "1") (pinfunction "1_1") (pintype "passive"))
      (node (ref "C50") (pin "1") (pinfunction "1_1") (pintype "passive"))
      (node (ref "C51") (pin "1") (pinfunction "1_1") (pintype "passive"))
      (node (ref "C52") (pin "1") (pinfunction "1_1") (pintype "passive"))
      (node (ref "C53") (pin "1") (pinfunction "1_1") (pintype "passive"))
      (node (ref "C54") (pin "1") (pinfunction "1_1") (pintype "passive"))
      (node (ref "C55") (pin "1") (pinfunction "1_1") (pintype "passive"))
      (node (ref "C56") (pin "1") (pinfunction "1_1") (pintype "passive"))
      (node (ref "C57") (pin "1") (pinfunction "1_1") (pintype "passive"))
      (node (ref "C58") (pin "1") (pinfunction "1_1") (pintype "passive"))
      (node (ref "C61") (pin "1") (pinfunction "1_1") (pintype "passive"))
      (node (ref "C62") (pin "1") (pinfunction "1_1") (pintype "passive"))
      (node (ref "C63") (pin "1") (pinfunction "1_1") (pintype "passive"))
      (node (ref "C64") (pin "2") (pinfunction "2_2") (pintype "passive"))
      (node (ref "C65") (pin "1") (pinfunction "1_1") (pintype "passive"))
      (node (ref "C66") (pin "1") (pinfunction "1_1") (pintype "passive"))
      (node (ref "D10") (pin "K") (pinfunction "K_K") (pintype "passive"))
      (node (ref "D11") (pin "K") (pinfunction "K_K") (pintype "passive"))
      (node (ref "D9") (pin "K") (pinfunction "K_K") (pintype "passive"))
      (node (ref "J3") (pin "2") (pinfunction "2_2") (pintype "passive"))
      (node (ref "J3") (pin "3") (pinfunction "3_3") (pintype "passive"))
      (node (ref "J3") (pin "4") (pinfunction "4_4") (pintype "passive"))
      (node (ref "J3") (pin "5") (pinfunction "5_5") (pintype "passive"))
      (node (ref "R35") (pin "1") (pinfunction "1_1") (pintype "passive"))
      (node (ref "RF1") (pin "1") (pinfunction "GND_1") (pintype "passive"))
      (node (ref "T1") (pin "2") (pinfunction "GND_2") (pintype "passive"))
      (node (ref "T1") (pin "5") (pinfunction "5_5") (pintype "passive"))
      (node (ref "U19") (pin "22") (pinfunction "FORCEON_22") (pintype "passive"))
      (node (ref "U19") (pin "23") (pinfunction "WAKEUP_23") (pintype "passive"))
      (node (ref "U19") (pin "32") (pinfunction "VSSIO_32") (pintype "passive"))
      (node (ref "U19") (pin "43") (pinfunction "VSSIO_43") (pintype "passive"))
      (node (ref "U19") (pin "46") (pinfunction "TESTMODE_46") (pintype "passive"))
      (node (ref "U19") (pin "49") (pinfunction "GND_49") (pintype "passive"))
    )
    (net (code "24") (name "Net-(C58-Pad2)") (class "Default")
      (node (ref "C58") (pin "2") (pinfunction "2_2") (pintype "passive"))
      (node (ref "U19") (pin "31") (pinfunction "VDDIO_31") (pintype "passive"))
    )
    (net (code "25") (name "Net-(C59-Pad1)") (class "Default")
      (node (ref "C59") (pin "1") (pinfunction "1_1") (pintype "passive"))
      (node (ref "T1") (pin "4") (pinfunction "4_4") (pintype "passive"))
    )
    (net (code "26") (name "Net-(C60-Pad1)") (class "Default")
      (node (ref "C60") (pin "1") (pinfunction "1_1") (pintype "passive"))
      (node (ref "T1") (pin "3") (pinfunction "3_3") (pintype "passive"))
    )
    (net (code "27") (name "Net-(C61-Pad2)") (class "Default")
      (node (ref "C61") (pin "2") (pinfunction "2_2") (pintype "passive"))
      (node (ref "U19") (pin "42") (pinfunction "VDDIO_42") (pintype "passive"))
    )
    (net (code "28") (name "Net-(C68-Pad2)") (class "Default")
      (node (ref "C68") (pin "2") (pinfunction "2_2") (pintype "passive"))
      (node (ref "R36") (pin "2") (pinfunction "2_2") (pintype "passive"))
    )
    (net (code "29") (name "Net-(C70-Pad2)") (class "Default")
      (node (ref "C70") (pin "2") (pinfunction "2_2") (pintype "passive"))
      (node (ref "R37") (pin "1") (pinfunction "1_1") (pintype "passive"))
    )
    (net (code "30") (name "Net-(D9-PadA)") (class "Default")
      (node (ref "D9") (pin "A") (pinfunction "A_A") (pintype "passive"))
      (node (ref "R33") (pin "1") (pinfunction "1_1") (pintype "passive"))
    )
    (net (code "31") (name "Net-(D10-PadA)") (class "Default")
      (node (ref "D10") (pin "A") (pinfunction "A_A") (pintype "passive"))
      (node (ref "R32") (pin "1") (pinfunction "1_1") (pintype "passive"))
    )
    (net (code "32") (name "Net-(D11-PadA)") (class "Default")
      (node (ref "D11") (pin "A") (pinfunction "A_A") (pintype "passive"))
      (node (ref "R34") (pin "1") (pinfunction "1_1") (pintype "passive"))
    )
    (net (code "33") (name "Net-(J3-Pad1)") (class "Default")
      (node (ref "J3") (pin "1") (pinfunction "1_1") (pintype "passive"))
      (node (ref "T1") (pin "1") (pinfunction "1_1") (pintype "passive"))
    )
    (net (code "34") (name "Net-(U19-CLKTUNE)") (class "Default")
      (node (ref "C69") (pin "1") (pinfunction "1_1") (pintype "passive"))
      (node (ref "R36") (pin "1") (pinfunction "1_1") (pintype "passive"))
      (node (ref "U19") (pin "8") (pinfunction "CLKTUNE_8") (pintype "passive"))
    )
    (net (code "35") (name "Net-(U19-GPIO5_{slash}_EXTTXE_{slash}_SPIPOL)") (class "Default")
      (node (ref "R39") (pin "2") (pinfunction "2_2") (pintype "passive"))
      (node (ref "U19") (pin "33") (pinfunction "GPIO5_/_EXTTXE_/_SPIPOL_33") (pintype "passive"))
    )
    (net (code "36") (name "Net-(U19-GPIO6_{slash}_EXTRXE_{slash}_SPIPHA)") (class "Default")
      (node (ref "R38") (pin "2") (pinfunction "2_2") (pintype "passive"))
      (node (ref "U19") (pin "30") (pinfunction "GPIO6_/_EXTRXE_/_SPIPHA_30") (pintype "passive"))
    )
    (net (code "37") (name "Net-(U19-VCOTUNE)") (class "Default")
      (node (ref "C67") (pin "2") (pinfunction "2_2") (pintype "passive"))
      (node (ref "R37") (pin "2") (pinfunction "2_2") (pintype "passive"))
      (node (ref "U19") (pin "12") (pinfunction "VCOTUNE_12") (pintype "passive"))
    )
    (net (code "38") (name "Net-(U19-VDDDIG)") (class "Default")
      (node (ref "C56") (pin "2") (pinfunction "2_2") (pintype "passive"))
      (node (ref "C63") (pin "2") (pinfunction "2_2") (pintype "passive"))
      (node (ref "U19") (pin "20") (pinfunction "VDDREG_20") (pintype "passive"))
      (node (ref "U19") (pin "44") (pinfunction "VDDDIG_44") (pintype "passive"))
    )
    (net (code "39") (name "Net-(U19-VDDIOA)") (class "Default")
      (node (ref "C64") (pin "1") (pinfunction "1_1") (pintype "passive"))
      (node (ref "U19") (pin "28") (pinfunction "VDDIOA_28") (pintype "passive"))
    )
    (net (code "40") (name "Net-(U19-VREF)") (class "Default")
      (node (ref "R35") (pin "2") (pinfunction "2_2") (pintype "passive"))
      (node (ref "U19") (pin "5") (pinfunction "VREF_5") (pintype "passive"))
    )
    (net (code "41") (name "Net-(U19-XTAL2)") (class "Default")
      (node (ref "C65") (pin "2") (pinfunction "2_2") (pintype "passive"))
      (node (ref "U19") (pin "4") (pinfunction "XTAL2_4") (pintype "passive"))
    )
    (net (code "42") (name "unconnected-(T1-NC-Pad6)") (class "Default")
      (node (ref "T1") (pin "6") (pinfunction "NC_6") (pintype "passive+no_connect"))
    )
    (net (code "43") (name "unconnected-(U19-GPIO0_{slash}_RXOKLED-Pad38)") (class "Default")
      (node (ref "U19") (pin "38") (pinfunction "GPIO0_/_RXOKLED_38") (pintype "passive+no_connect"))
    )
    (net (code "44") (name "unconnected-(U19-GPIO1_{slash}_SFDLED-Pad37)") (class "Default")
      (node (ref "U19") (pin "37") (pinfunction "GPIO1_/_SFDLED_37") (pintype "passive+no_connect"))
    )
    (net (code "45") (name "unconnected-(U19-GPIO4_{slash}_EXTPA-Pad34)") (class "Default")
      (node (ref "U19") (pin "34") (pinfunction "GPIO4_/_EXTPA_34") (pintype "passive+no_connect"))
    )
    (net (code "46") (name "unconnected-(U19-NC-Pad1)") (class "Default")
      (node (ref "U19") (pin "1") (pinfunction "NC_1") (pintype "passive+no_connect"))
    )
    (net (code "47") (name "unconnected-(U19-NC-Pad2)") (class "Default")
      (node (ref "U19") (pin "2") (pinfunction "NC_2") (pintype "passive+no_connect"))
    )
    (net (code "48") (name "unconnected-(U19-NC-Pad13)") (class "Default")
      (node (ref "U19") (pin "13") (pinfunction "NC_13") (pintype "passive+no_connect"))
    )
    (net (code "49") (name "unconnected-(U19-NC-Pad14)") (class "Default")
      (node (ref "U19") (pin "14") (pinfunction "NC_14") (pintype "passive+no_connect"))
    )
  )
)
